# Qwiic_Spectral_Sensor_AS7341.net
KiCad netlist of a schematic drawn in EAGLE
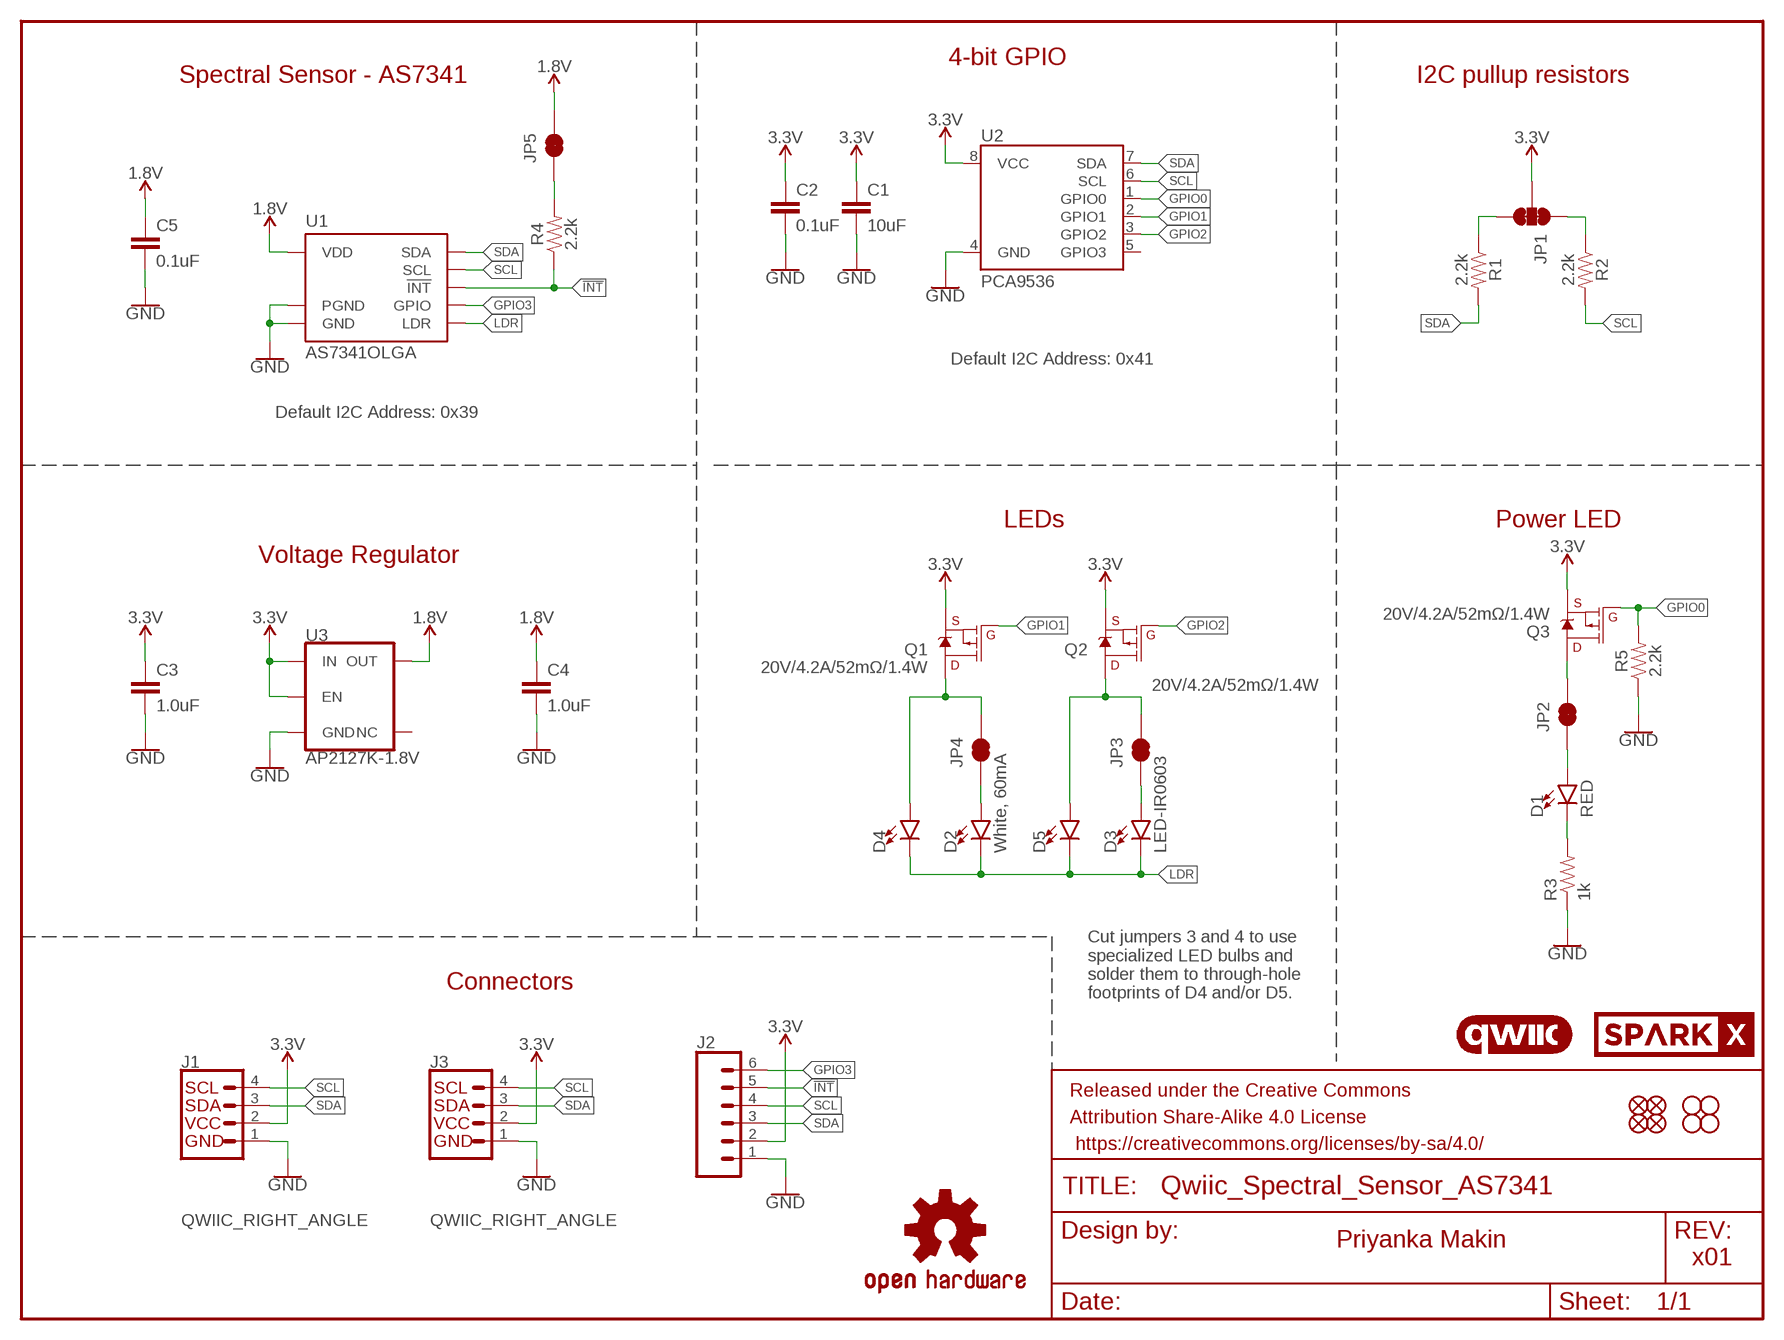
[diagram p0: schematic, sheet 1]

(export (version "E")
  (design (tool "Eeschema 10.0.6"))
  (components
    (comp (ref "C1")
      (value "10uF")
      (footprint "eagle-import:0603")
      (libsource (lib "eagle-import") (part "10UF-0603-6.3V-20%"))
    )
    (comp (ref "C2")
      (value "0.1uF")
      (footprint "eagle-import:0603")
      (libsource (lib "eagle-import") (part "0.1UF-0603-25V-(+80/-20%)"))
    )
    (comp (ref "C3")
      (value "1.0uF")
      (footprint "eagle-import:0603")
      (libsource (lib "eagle-import") (part "1.0UF-0603-16V-10%"))
    )
    (comp (ref "C4")
      (value "1.0uF")
      (footprint "eagle-import:0603")
      (libsource (lib "eagle-import") (part "1.0UF-0603-16V-10%"))
    )
    (comp (ref "C5")
      (value "0.1uF")
      (footprint "eagle-import:0603")
      (libsource (lib "eagle-import") (part "0.1UF-0603-25V-(+80/-20%)"))
    )
    (comp (ref "D1")
      (value "RED")
      (footprint "eagle-import:LED-0603")
      (libsource (lib "eagle-import") (part "LED-RED0603"))
    )
    (comp (ref "D2")
      (value "White, 60mA")
      (footprint "eagle-import:SUPER_BRIGHT_SMD_LED_3014")
      (libsource (lib "eagle-import") (part "LED-WHITE3014"))
    )
    (comp (ref "D3")
      (value "LED-IR0603")
      (footprint "eagle-import:LED-0603")
      (libsource (lib "eagle-import") (part "LED-IR0603"))
    )
    (comp (ref "D4")
      (value "LED-3MM-NO_SILK")
      (footprint "eagle-import:LED_3MM-NS")
      (libsource (lib "eagle-import") (part "LED-3MM-NO_SILK"))
    )
    (comp (ref "D5")
      (value "LED-3MM-NO_SILK")
      (footprint "eagle-import:LED_3MM-NS")
      (libsource (lib "eagle-import") (part "LED-3MM-NO_SILK"))
    )
    (comp (ref "FD1")
      (value "FIDUCIAL1X2")
      (footprint "eagle-import:FIDUCIAL-1X2")
      (libsource (lib "eagle-import") (part "FIDUCIAL1X2"))
    )
    (comp (ref "FD2")
      (value "FIDUCIAL1X2")
      (footprint "eagle-import:FIDUCIAL-1X2")
      (libsource (lib "eagle-import") (part "FIDUCIAL1X2"))
    )
    (comp (ref "FD3")
      (value "FIDUCIAL1X2")
      (footprint "eagle-import:FIDUCIAL-1X2")
      (libsource (lib "eagle-import") (part "FIDUCIAL1X2"))
    )
    (comp (ref "FD4")
      (value "FIDUCIAL1X2")
      (footprint "eagle-import:FIDUCIAL-1X2")
      (libsource (lib "eagle-import") (part "FIDUCIAL1X2"))
    )
    (comp (ref "FRAME1")
      (value "FRAME-LETTER")
      (footprint "eagle-import:CREATIVE_COMMONS")
      (libsource (lib "eagle-import") (part "FRAME-LETTER"))
    )
    (comp (ref "H1")
      (value "STAND-OFF")
      (footprint "eagle-import:STAND-OFF")
      (libsource (lib "eagle-import") (part "STAND-OFF"))
    )
    (comp (ref "H2")
      (value "STAND-OFF")
      (footprint "eagle-import:STAND-OFF")
      (libsource (lib "eagle-import") (part "STAND-OFF"))
    )
    (comp (ref "H3")
      (value "STAND-OFF")
      (footprint "eagle-import:STAND-OFF")
      (libsource (lib "eagle-import") (part "STAND-OFF"))
    )
    (comp (ref "H4")
      (value "STAND-OFF")
      (footprint "eagle-import:STAND-OFF")
      (libsource (lib "eagle-import") (part "STAND-OFF"))
    )
    (comp (ref "J1")
      (value "QWIIC_RIGHT_ANGLE")
      (footprint "eagle-import:JST04_1MM_RA")
      (libsource (lib "eagle-import") (part "QWIIC_CONNECTORJS-1MM"))
    )
    (comp (ref "J2")
      (value "CONN_06NO_SILK_FEMALE_PTH")
      (footprint "eagle-import:1X06_NO_SILK")
      (libsource (lib "eagle-import") (part "CONN_06NO_SILK_FEMALE_PTH"))
    )
    (comp (ref "J3")
      (value "QWIIC_RIGHT_ANGLE")
      (footprint "eagle-import:JST04_1MM_RA")
      (libsource (lib "eagle-import") (part "QWIIC_CONNECTORJS-1MM"))
    )
    (comp (ref "JP1")
      (value "JUMPER-SMT_3_2-NC_TRACE_SILK")
      (footprint "eagle-import:SMT-JUMPER_3_2-NC_TRACE_SILK")
      (libsource (lib "eagle-import") (part "JUMPER-SMT_3_2-NC_TRACE_SILK"))
    )
    (comp (ref "JP2")
      (value "JUMPER-SMT_2_NC_TRACE_SILK")
      (footprint "eagle-import:SMT-JUMPER_2_NC_TRACE_SILK")
      (libsource (lib "eagle-import") (part "JUMPER-SMT_2_NC_TRACE_SILK"))
    )
    (comp (ref "JP3")
      (value "JUMPER-SMT_2_NC_TRACE_SILK")
      (footprint "eagle-import:SMT-JUMPER_2_NC_TRACE_SILK")
      (libsource (lib "eagle-import") (part "JUMPER-SMT_2_NC_TRACE_SILK"))
    )
    (comp (ref "JP4")
      (value "JUMPER-SMT_2_NC_TRACE_SILK")
      (footprint "eagle-import:SMT-JUMPER_2_NC_TRACE_SILK")
      (libsource (lib "eagle-import") (part "JUMPER-SMT_2_NC_TRACE_SILK"))
    )
    (comp (ref "JP5")
      (value "JUMPER-SMT_2_NC_TRACE_SILK")
      (footprint "eagle-import:SMT-JUMPER_2_NC_TRACE_SILK")
      (libsource (lib "eagle-import") (part "JUMPER-SMT_2_NC_TRACE_SILK"))
    )
    (comp (ref "LOGO1")
      (value "QWIIC_LOGO_6MM")
      (footprint "eagle-import:QWIIC_6MM")
      (libsource (lib "eagle-import") (part "QWIIC_LOGO_6MM"))
    )
    (comp (ref "Q1")
      (value "20V/4.2A/52mΩ/1.4W")
      (footprint "eagle-import:SOT23-3")
      (libsource (lib "eagle-import") (part "MOSFET_PCH-DMG2305UX-7"))
    )
    (comp (ref "Q2")
      (value "20V/4.2A/52mΩ/1.4W")
      (footprint "eagle-import:SOT23-3")
      (libsource (lib "eagle-import") (part "MOSFET_PCH-DMG2305UX-7"))
    )
    (comp (ref "Q3")
      (value "20V/4.2A/52mΩ/1.4W")
      (footprint "eagle-import:SOT23-3")
      (libsource (lib "eagle-import") (part "MOSFET_PCH-DMG2305UX-7"))
    )
    (comp (ref "R1")
      (value "2.2k")
      (footprint "eagle-import:0603")
      (libsource (lib "eagle-import") (part "2.2KOHM-0603-1/10W-1%"))
    )
    (comp (ref "R2")
      (value "2.2k")
      (footprint "eagle-import:0603")
      (libsource (lib "eagle-import") (part "2.2KOHM-0603-1/10W-1%"))
    )
    (comp (ref "R3")
      (value "1k")
      (footprint "eagle-import:0603")
      (libsource (lib "eagle-import") (part "1KOHM-0603-1/10W-1%"))
    )
    (comp (ref "R4")
      (value "2.2k")
      (footprint "eagle-import:0603")
      (libsource (lib "eagle-import") (part "2.2KOHM-0603-1/10W-1%"))
    )
    (comp (ref "R5")
      (value "2.2k")
      (footprint "eagle-import:0603")
      (libsource (lib "eagle-import") (part "2.2KOHM-0603-1/10W-1%"))
    )
    (comp (ref "U$1")
      (value "OSHW-LOGOS")
      (footprint "eagle-import:OSHW-LOGO-S")
      (libsource (lib "eagle-import") (part "OSHW-LOGOS"))
    )
    (comp (ref "U$31")
      (value "SPARKX-LOGO3")
      (footprint "eagle-import:SPARKX-SMALL")
      (libsource (lib "eagle-import") (part "SPARKX-LOGO3"))
    )
    (comp (ref "U1")
      (value "AS7341OLGA")
      (footprint "eagle-import:OLGA8")
      (libsource (lib "eagle-import") (part "AS7341OLGA"))
    )
    (comp (ref "U2")
      (value "PCA9536")
      (footprint "eagle-import:MSOP8")
      (libsource (lib "eagle-import") (part "PCA9536"))
    )
    (comp (ref "U3")
      (value "AP2127K-1.8V")
      (footprint "eagle-import:SOT23-5")
      (libsource (lib "eagle-import") (part "V_REG_AP2127K-1.8V"))
    )
  )
  (nets
    (net (code "1") (name "/~{INT}") (class "Default")
      (node (ref "J2") (pin "5") (pinfunction "5_5") (pintype "passive"))
      (node (ref "R4") (pin "1") (pinfunction "1_1") (pintype "passive"))
      (node (ref "U1") (pin "7") (pinfunction "~{INT}_7") (pintype "bidirectional"))
    )
    (net (code "2") (name "1.8V") (class "Default")
      (node (ref "C4") (pin "1") (pinfunction "1_1") (pintype "passive"))
      (node (ref "C5") (pin "1") (pinfunction "1_1") (pintype "passive"))
      (node (ref "JP5") (pin "2") (pinfunction "2_2") (pintype "passive"))
      (node (ref "U1") (pin "1") (pinfunction "VDD_1") (pintype "power_in"))
      (node (ref "U3") (pin "5") (pinfunction "OUT_5") (pintype "passive"))
    )
    (net (code "3") (name "3.3V") (class "Default")
      (node (ref "C1") (pin "1") (pinfunction "1_1") (pintype "passive"))
      (node (ref "C2") (pin "1") (pinfunction "1_1") (pintype "passive"))
      (node (ref "C3") (pin "1") (pinfunction "1_1") (pintype "passive"))
      (node (ref "J1") (pin "2") (pinfunction "2_2") (pintype "power_in"))
      (node (ref "J2") (pin "2") (pinfunction "2_2") (pintype "passive"))
      (node (ref "J3") (pin "2") (pinfunction "2_2") (pintype "power_in"))
      (node (ref "JP1") (pin "2") (pinfunction "2_2") (pintype "passive"))
      (node (ref "Q1") (pin "2") (pinfunction "S_2") (pintype "bidirectional"))
      (node (ref "Q2") (pin "2") (pinfunction "S_2") (pintype "bidirectional"))
      (node (ref "Q3") (pin "2") (pinfunction "S_2") (pintype "bidirectional"))
      (node (ref "U2") (pin "8") (pinfunction "VCC_8") (pintype "bidirectional"))
      (node (ref "U3") (pin "1") (pinfunction "IN_1") (pintype "input"))
      (node (ref "U3") (pin "3") (pinfunction "EN_3") (pintype "input"))
    )
    (net (code "4") (name "GND") (class "Default")
      (node (ref "C1") (pin "2") (pinfunction "2_2") (pintype "passive"))
      (node (ref "C2") (pin "2") (pinfunction "2_2") (pintype "passive"))
      (node (ref "C3") (pin "2") (pinfunction "2_2") (pintype "passive"))
      (node (ref "C4") (pin "2") (pinfunction "2_2") (pintype "passive"))
      (node (ref "C5") (pin "2") (pinfunction "2_2") (pintype "passive"))
      (node (ref "J1") (pin "1") (pinfunction "1_1") (pintype "power_in"))
      (node (ref "J2") (pin "1") (pinfunction "1_1") (pintype "passive"))
      (node (ref "J3") (pin "1") (pinfunction "1_1") (pintype "power_in"))
      (node (ref "R3") (pin "1") (pinfunction "1_1") (pintype "passive"))
      (node (ref "R5") (pin "1") (pinfunction "1_1") (pintype "passive"))
      (node (ref "U1") (pin "3") (pinfunction "GND_3") (pintype "power_in"))
      (node (ref "U1") (pin "5") (pinfunction "PGND_5") (pintype "power_in"))
      (node (ref "U2") (pin "4") (pinfunction "GND_4") (pintype "bidirectional"))
      (node (ref "U3") (pin "2") (pinfunction "GND_2") (pintype "input"))
    )
    (net (code "5") (name "GPIO0") (class "Default")
      (node (ref "Q3") (pin "1") (pinfunction "G_1") (pintype "bidirectional"))
      (node (ref "R5") (pin "2") (pinfunction "2_2") (pintype "passive"))
      (node (ref "U2") (pin "1") (pinfunction "GPIO0_1") (pintype "bidirectional"))
    )
    (net (code "6") (name "GPIO1") (class "Default")
      (node (ref "Q1") (pin "1") (pinfunction "G_1") (pintype "bidirectional"))
      (node (ref "U2") (pin "2") (pinfunction "GPIO1_2") (pintype "bidirectional"))
    )
    (net (code "7") (name "GPIO2") (class "Default")
      (node (ref "Q2") (pin "1") (pinfunction "G_1") (pintype "bidirectional"))
      (node (ref "U2") (pin "3") (pinfunction "GPIO2_3") (pintype "bidirectional"))
    )
    (net (code "8") (name "GPIO3") (class "Default")
      (node (ref "J2") (pin "6") (pinfunction "6_6") (pintype "passive"))
      (node (ref "U1") (pin "6") (pinfunction "GPIO_6") (pintype "bidirectional"))
    )
    (net (code "9") (name "LDR") (class "Default")
      (node (ref "D2") (pin "C") (pinfunction "C_C") (pintype "passive"))
      (node (ref "D3") (pin "C") (pinfunction "C_C") (pintype "passive"))
      (node (ref "D4") (pin "K") (pinfunction "C_K") (pintype "passive"))
      (node (ref "D5") (pin "K") (pinfunction "C_K") (pintype "passive"))
      (node (ref "U1") (pin "4") (pinfunction "LDR_4") (pintype "bidirectional"))
    )
    (net (code "10") (name "Net-(D1-PadA)") (class "Default")
      (node (ref "D1") (pin "A") (pinfunction "A_A") (pintype "passive"))
      (node (ref "JP2") (pin "1") (pinfunction "1_1") (pintype "passive"))
    )
    (net (code "11") (name "Net-(D1-PadC)") (class "Default")
      (node (ref "D1") (pin "C") (pinfunction "C_C") (pintype "passive"))
      (node (ref "R3") (pin "2") (pinfunction "2_2") (pintype "passive"))
    )
    (net (code "12") (name "Net-(D2-PadA)") (class "Default")
      (node (ref "D2") (pin "A") (pinfunction "A_A") (pintype "passive"))
      (node (ref "JP4") (pin "1") (pinfunction "1_1") (pintype "passive"))
    )
    (net (code "13") (name "Net-(D3-PadA)") (class "Default")
      (node (ref "D3") (pin "A") (pinfunction "A_A") (pintype "passive"))
      (node (ref "JP3") (pin "1") (pinfunction "1_1") (pintype "passive"))
    )
    (net (code "14") (name "Net-(JP1-Pad1)") (class "Default")
      (node (ref "JP1") (pin "1") (pinfunction "1_1") (pintype "passive"))
      (node (ref "R2") (pin "1") (pinfunction "1_1") (pintype "passive"))
    )
    (net (code "15") (name "Net-(JP1-Pad3)") (class "Default")
      (node (ref "JP1") (pin "3") (pinfunction "3_3") (pintype "passive"))
      (node (ref "R1") (pin "1") (pinfunction "1_1") (pintype "passive"))
    )
    (net (code "16") (name "Net-(JP5-Pad1)") (class "Default")
      (node (ref "JP5") (pin "1") (pinfunction "1_1") (pintype "passive"))
      (node (ref "R4") (pin "2") (pinfunction "2_2") (pintype "passive"))
    )
    (net (code "17") (name "Net-(Q1-D)") (class "Default")
      (node (ref "D4") (pin "A") (pinfunction "A_A") (pintype "passive"))
      (node (ref "JP4") (pin "2") (pinfunction "2_2") (pintype "passive"))
      (node (ref "Q1") (pin "3") (pinfunction "D_3") (pintype "bidirectional"))
    )
    (net (code "18") (name "Net-(Q2-D)") (class "Default")
      (node (ref "D5") (pin "A") (pinfunction "A_A") (pintype "passive"))
      (node (ref "JP3") (pin "2") (pinfunction "2_2") (pintype "passive"))
      (node (ref "Q2") (pin "3") (pinfunction "D_3") (pintype "bidirectional"))
    )
    (net (code "19") (name "Net-(Q3-D)") (class "Default")
      (node (ref "JP2") (pin "2") (pinfunction "2_2") (pintype "passive"))
      (node (ref "Q3") (pin "3") (pinfunction "D_3") (pintype "bidirectional"))
    )
    (net (code "20") (name "SCL") (class "Default")
      (node (ref "J1") (pin "4") (pinfunction "4_4") (pintype "passive"))
      (node (ref "J2") (pin "4") (pinfunction "4_4") (pintype "passive"))
      (node (ref "J3") (pin "4") (pinfunction "4_4") (pintype "passive"))
      (node (ref "R2") (pin "2") (pinfunction "2_2") (pintype "passive"))
      (node (ref "U1") (pin "2") (pinfunction "SCL_2") (pintype "bidirectional"))
      (node (ref "U2") (pin "6") (pinfunction "SCL_6") (pintype "bidirectional"))
    )
    (net (code "21") (name "SDA") (class "Default")
      (node (ref "J1") (pin "3") (pinfunction "3_3") (pintype "passive"))
      (node (ref "J2") (pin "3") (pinfunction "3_3") (pintype "passive"))
      (node (ref "J3") (pin "3") (pinfunction "3_3") (pintype "passive"))
      (node (ref "R1") (pin "2") (pinfunction "2_2") (pintype "passive"))
      (node (ref "U1") (pin "8") (pinfunction "SDA_8") (pintype "bidirectional"))
      (node (ref "U2") (pin "7") (pinfunction "SDA_7") (pintype "bidirectional"))
    )
    (net (code "22") (name "unconnected-(U2-GPIO3-Pad5)") (class "Default")
      (node (ref "U2") (pin "5") (pinfunction "GPIO3_5") (pintype "bidirectional"))
    )
    (net (code "23") (name "unconnected-(U3-NC-Pad4)") (class "Default")
      (node (ref "U3") (pin "4") (pinfunction "NC_4") (pintype "no_connect"))
    )
  )
)
